# 00B-001.net
KiCad netlist of a schematic drawn in EAGLE
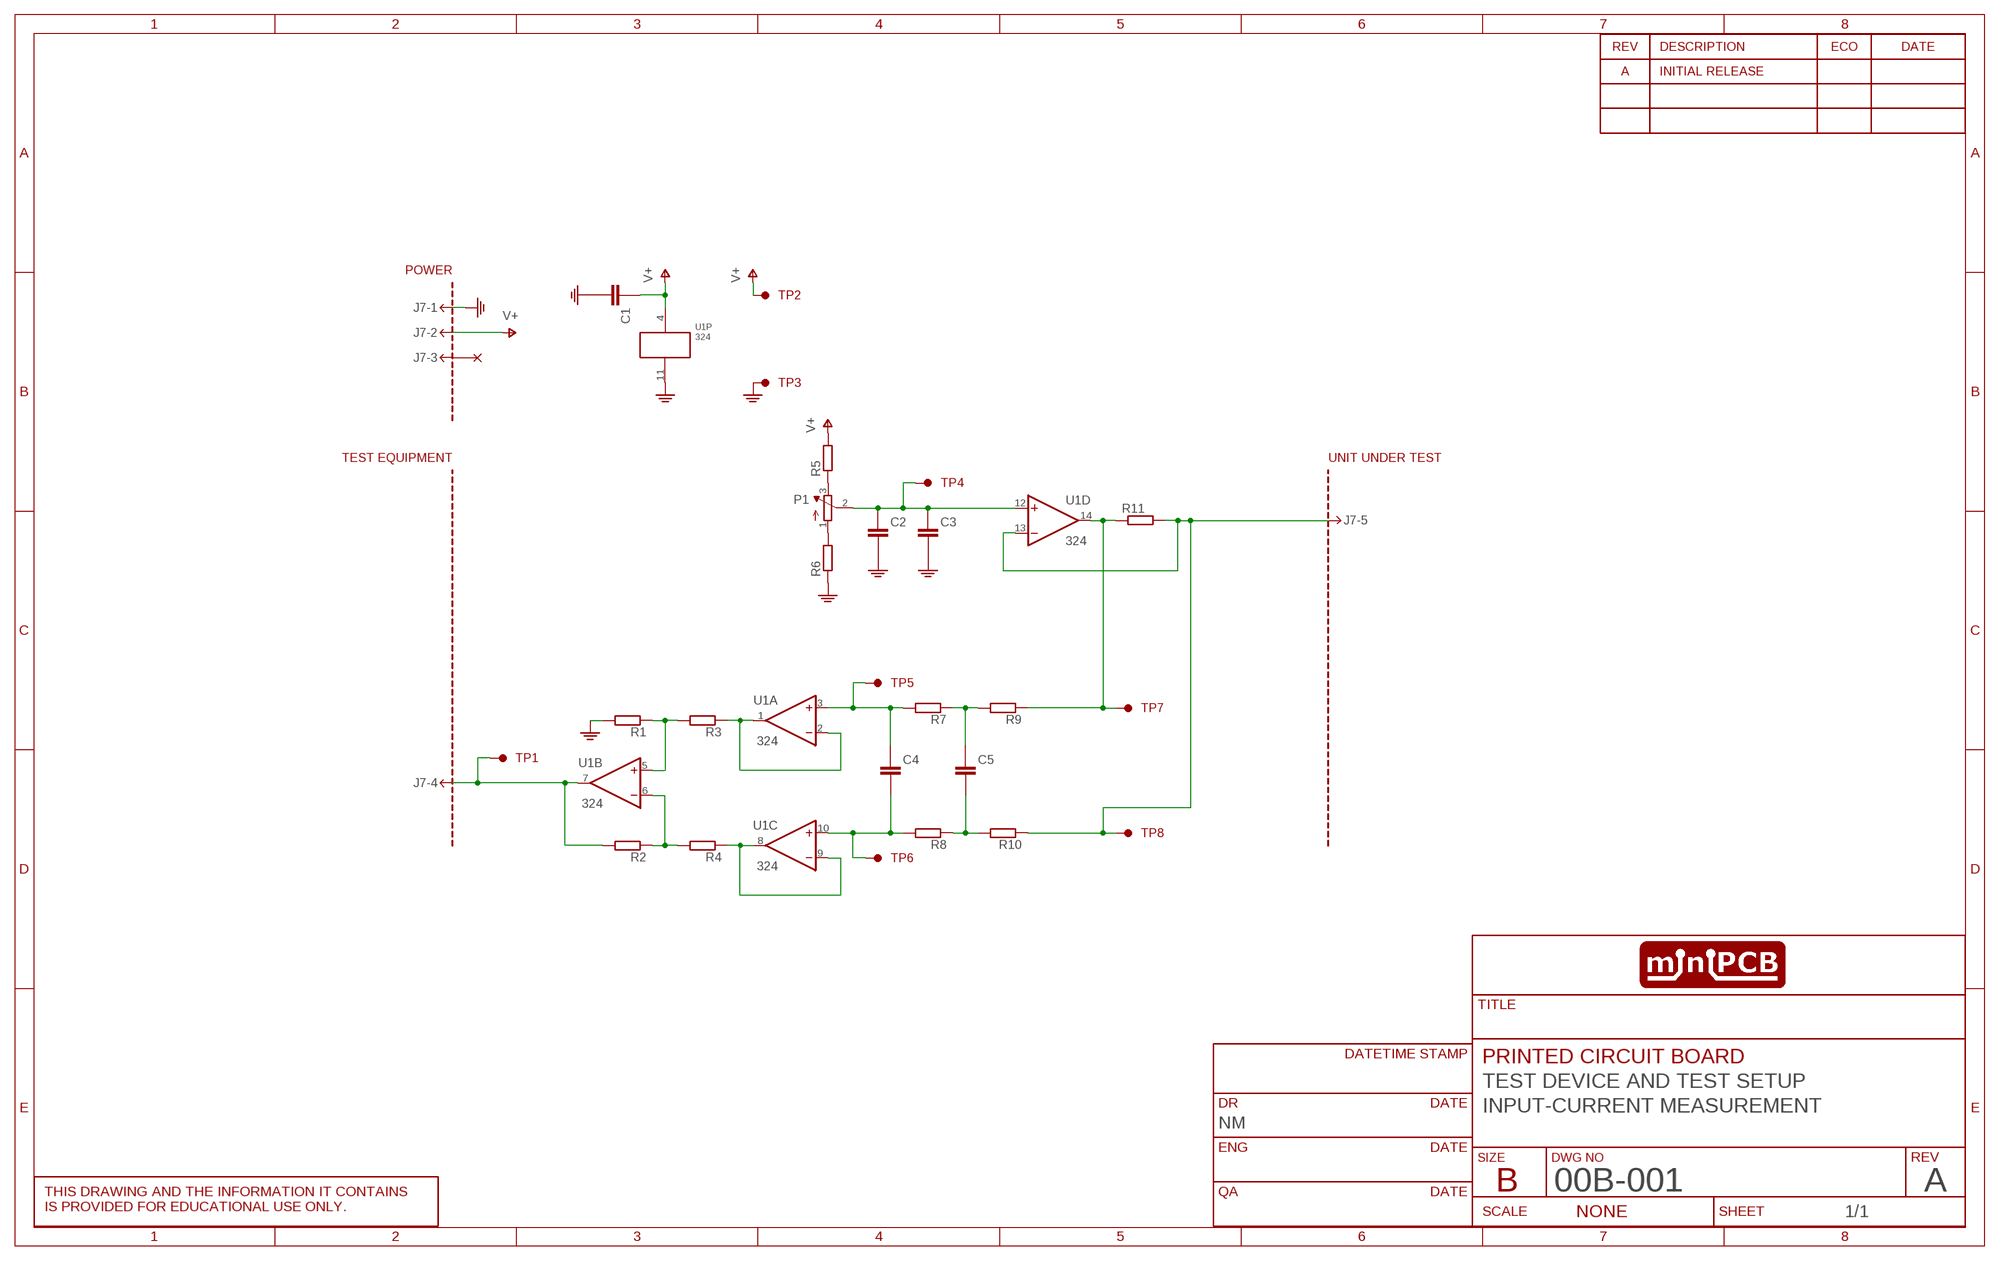
[diagram p0: schematic, sheet 1]

(export (version "E")
  (design (tool "Eeschema 10.0.6"))
  (components
    (comp (ref "C1")
      (value "1u")
      (footprint "eagle-import:C050-024X044")
      (libsource (lib "eagle-import") (part "CAPACITORTHD"))
    )
    (comp (ref "C2")
      (value "CAPACITOR_10")
      (footprint "eagle-import:C5MM")
      (libsource (lib "eagle-import") (part "CAPACITOR_10"))
    )
    (comp (ref "C3")
      (value "CAPACITORTHD")
      (footprint "eagle-import:C050-024X044")
      (libsource (lib "eagle-import") (part "CAPACITORTHD"))
    )
    (comp (ref "C4")
      (value "CAPACITORTHD")
      (footprint "eagle-import:C050-024X044")
      (libsource (lib "eagle-import") (part "CAPACITORTHD"))
    )
    (comp (ref "C5")
      (value "CAPACITORTHD")
      (footprint "eagle-import:C050-024X044")
      (libsource (lib "eagle-import") (part "CAPACITORTHD"))
    )
    (comp (ref "J7-")
      (value "MINIPCB_5P50X50")
      (footprint "eagle-import:MINIPCB_5P_50X50MM")
      (fields (field (name "PART_NUMBER") "00B-001"))
      (libsource (lib "eagle-import") (part "MINIPCB_5P50X50"))
    )
    (comp (ref "P1")
      (value "TRIMPOT0.100THD")
      (footprint "eagle-import:TRIM_0100")
      (libsource (lib "eagle-import") (part "TRIMPOT0.100THD"))
    )
    (comp (ref "R1")
      (value "RESISTOR10MM")
      (footprint "eagle-import:0207_10")
      (libsource (lib "eagle-import") (part "RESISTOR10MM"))
    )
    (comp (ref "R2")
      (value "RESISTOR10MM")
      (footprint "eagle-import:0207_10")
      (libsource (lib "eagle-import") (part "RESISTOR10MM"))
    )
    (comp (ref "R3")
      (value "RESISTOR10MM")
      (footprint "eagle-import:0207_10")
      (libsource (lib "eagle-import") (part "RESISTOR10MM"))
    )
    (comp (ref "R4")
      (value "RESISTOR10MM")
      (footprint "eagle-import:0207_10")
      (libsource (lib "eagle-import") (part "RESISTOR10MM"))
    )
    (comp (ref "R5")
      (value "RESISTOR10MM")
      (footprint "eagle-import:0207_10")
      (libsource (lib "eagle-import") (part "RESISTOR10MM"))
    )
    (comp (ref "R6")
      (value "RESISTOR10MM")
      (footprint "eagle-import:0207_10")
      (libsource (lib "eagle-import") (part "RESISTOR10MM"))
    )
    (comp (ref "R7")
      (value "RESISTOR10MM")
      (footprint "eagle-import:0207_10")
      (libsource (lib "eagle-import") (part "RESISTOR10MM"))
    )
    (comp (ref "R8")
      (value "RESISTOR10MM")
      (footprint "eagle-import:0207_10")
      (libsource (lib "eagle-import") (part "RESISTOR10MM"))
    )
    (comp (ref "R9")
      (value "RESISTOR10MM")
      (footprint "eagle-import:0207_10")
      (libsource (lib "eagle-import") (part "RESISTOR10MM"))
    )
    (comp (ref "R10")
      (value "RESISTOR10MM")
      (footprint "eagle-import:0207_10")
      (libsource (lib "eagle-import") (part "RESISTOR10MM"))
    )
    (comp (ref "R11")
      (value "RESISTOR10MM")
      (footprint "eagle-import:0207_10")
      (libsource (lib "eagle-import") (part "RESISTOR10MM"))
    )
    (comp (ref "TP1")
      (value "TESTPOINTKE5000-SMTEXT")
      (footprint "eagle-import:PINS_1_TESTPOINT_KE5000_NOTEXT")
      (libsource (lib "eagle-import") (part "TESTPOINTKE5000-SMTEXT"))
    )
    (comp (ref "TP2")
      (value "TESTPOINTKE5000-SMTEXT")
      (footprint "eagle-import:PINS_1_TESTPOINT_KE5000_NOTEXT")
      (libsource (lib "eagle-import") (part "TESTPOINTKE5000-SMTEXT"))
    )
    (comp (ref "TP3")
      (value "TESTPOINTKE5000-SMTEXT")
      (footprint "eagle-import:PINS_1_TESTPOINT_KE5000_NOTEXT")
      (libsource (lib "eagle-import") (part "TESTPOINTKE5000-SMTEXT"))
    )
    (comp (ref "TP4")
      (value "TESTPOINTKE5000-SMTEXT")
      (footprint "eagle-import:PINS_1_TESTPOINT_KE5000_NOTEXT")
      (libsource (lib "eagle-import") (part "TESTPOINTKE5000-SMTEXT"))
    )
    (comp (ref "TP5")
      (value "TESTPOINTKE5000-SMTEXT")
      (footprint "eagle-import:PINS_1_TESTPOINT_KE5000_NOTEXT")
      (libsource (lib "eagle-import") (part "TESTPOINTKE5000-SMTEXT"))
    )
    (comp (ref "TP6")
      (value "TESTPOINTKE5000-SMTEXT")
      (footprint "eagle-import:PINS_1_TESTPOINT_KE5000_NOTEXT")
      (libsource (lib "eagle-import") (part "TESTPOINTKE5000-SMTEXT"))
    )
    (comp (ref "TP7")
      (value "TESTPOINTKE5000-SMTEXT")
      (footprint "eagle-import:PINS_1_TESTPOINT_KE5000_NOTEXT")
      (libsource (lib "eagle-import") (part "TESTPOINTKE5000-SMTEXT"))
    )
    (comp (ref "TP8")
      (value "TESTPOINTKE5000-SMTEXT")
      (footprint "eagle-import:PINS_1_TESTPOINT_KE5000_NOTEXT")
      (libsource (lib "eagle-import") (part "TESTPOINTKE5000-SMTEXT"))
    )
    (comp (ref "U1")
      (value "324")
      (footprint "eagle-import:DIL14")
      (libsource (lib "eagle-import") (part "OPAMP_QUADTHD"))
    )
  )
  (nets
    (net (code "1") (name "GND") (class "Default")
      (node (ref "C1") (pin "2") (pinfunction "-_2") (pintype "passive"))
      (node (ref "C2") (pin "-") (pinfunction "-_-") (pintype "passive"))
      (node (ref "C3") (pin "2") (pinfunction "-_2") (pintype "passive"))
      (node (ref "J7-") (pin "1") (pinfunction "1_1") (pintype "bidirectional"))
      (node (ref "R1") (pin "2") (pinfunction "2_2") (pintype "passive"))
      (node (ref "R6") (pin "1") (pinfunction "1_1") (pintype "passive"))
      (node (ref "TP3") (pin "1") (pinfunction "1_1") (pintype "bidirectional"))
      (node (ref "U1") (pin "11") (pinfunction "V-_11") (pintype "power_in"))
    )
    (net (code "2") (name "Net-(C3-+)") (class "Default")
      (node (ref "C2") (pin "+") (pinfunction "+_+") (pintype "passive"))
      (node (ref "C3") (pin "1") (pinfunction "+_1") (pintype "passive"))
      (node (ref "P1") (pin "2") (pinfunction "S_2") (pintype "passive"))
      (node (ref "TP4") (pin "1") (pinfunction "1_1") (pintype "bidirectional"))
      (node (ref "U1") (pin "12") (pinfunction "+IN_12") (pintype "input"))
    )
    (net (code "3") (name "Net-(C4-+)") (class "Default")
      (node (ref "C4") (pin "1") (pinfunction "+_1") (pintype "passive"))
      (node (ref "R7") (pin "2") (pinfunction "2_2") (pintype "passive"))
      (node (ref "TP5") (pin "1") (pinfunction "1_1") (pintype "bidirectional"))
      (node (ref "U1") (pin "3") (pinfunction "+IN_3") (pintype "input"))
    )
    (net (code "4") (name "Net-(C4--)") (class "Default")
      (node (ref "C4") (pin "2") (pinfunction "-_2") (pintype "passive"))
      (node (ref "R8") (pin "2") (pinfunction "2_2") (pintype "passive"))
      (node (ref "TP6") (pin "1") (pinfunction "1_1") (pintype "bidirectional"))
      (node (ref "U1") (pin "10") (pinfunction "+IN_10") (pintype "input"))
    )
    (net (code "5") (name "Net-(C5-+)") (class "Default")
      (node (ref "C5") (pin "1") (pinfunction "+_1") (pintype "passive"))
      (node (ref "R7") (pin "1") (pinfunction "1_1") (pintype "passive"))
      (node (ref "R9") (pin "2") (pinfunction "2_2") (pintype "passive"))
    )
    (net (code "6") (name "Net-(C5--)") (class "Default")
      (node (ref "C5") (pin "2") (pinfunction "-_2") (pintype "passive"))
      (node (ref "R10") (pin "2") (pinfunction "2_2") (pintype "passive"))
      (node (ref "R8") (pin "1") (pinfunction "1_1") (pintype "passive"))
    )
    (net (code "7") (name "Net-(J7-D-1)") (class "Default")
      (node (ref "J7-") (pin "4") (pinfunction "1_4") (pintype "bidirectional"))
      (node (ref "R2") (pin "2") (pinfunction "2_2") (pintype "passive"))
      (node (ref "TP1") (pin "1") (pinfunction "1_1") (pintype "bidirectional"))
      (node (ref "U1") (pin "7") (pinfunction "OUT_7") (pintype "output"))
    )
    (net (code "8") (name "Net-(J7-H-1)") (class "Default")
      (node (ref "J7-") (pin "5") (pinfunction "1_5") (pintype "bidirectional"))
      (node (ref "R10") (pin "1") (pinfunction "1_1") (pintype "passive"))
      (node (ref "R11") (pin "2") (pinfunction "2_2") (pintype "passive"))
      (node (ref "TP8") (pin "1") (pinfunction "1_1") (pintype "bidirectional"))
      (node (ref "U1") (pin "13") (pinfunction "-IN_13") (pintype "input"))
    )
    (net (code "9") (name "Net-(P1-A)") (class "Default")
      (node (ref "P1") (pin "1") (pinfunction "A_1") (pintype "passive"))
      (node (ref "R6") (pin "2") (pinfunction "2_2") (pintype "passive"))
    )
    (net (code "10") (name "Net-(P1-E)") (class "Default")
      (node (ref "P1") (pin "3") (pinfunction "E_3") (pintype "passive"))
      (node (ref "R5") (pin "1") (pinfunction "1_1") (pintype "passive"))
    )
    (net (code "11") (name "Net-(U1A--IN)") (class "Default")
      (node (ref "R3") (pin "1") (pinfunction "1_1") (pintype "passive"))
      (node (ref "U1") (pin "1") (pinfunction "OUT_1") (pintype "output"))
      (node (ref "U1") (pin "2") (pinfunction "-IN_2") (pintype "input"))
    )
    (net (code "12") (name "Net-(U1B-+IN)") (class "Default")
      (node (ref "R1") (pin "1") (pinfunction "1_1") (pintype "passive"))
      (node (ref "R3") (pin "2") (pinfunction "2_2") (pintype "passive"))
      (node (ref "U1") (pin "5") (pinfunction "+IN_5") (pintype "input"))
    )
    (net (code "13") (name "Net-(U1B--IN)") (class "Default")
      (node (ref "R2") (pin "1") (pinfunction "1_1") (pintype "passive"))
      (node (ref "R4") (pin "2") (pinfunction "2_2") (pintype "passive"))
      (node (ref "U1") (pin "6") (pinfunction "-IN_6") (pintype "input"))
    )
    (net (code "14") (name "Net-(U1C--IN)") (class "Default")
      (node (ref "R4") (pin "1") (pinfunction "1_1") (pintype "passive"))
      (node (ref "U1") (pin "8") (pinfunction "OUT_8") (pintype "output"))
      (node (ref "U1") (pin "9") (pinfunction "-IN_9") (pintype "input"))
    )
    (net (code "15") (name "Net-(U1D-OUT)") (class "Default")
      (node (ref "R11") (pin "1") (pinfunction "1_1") (pintype "passive"))
      (node (ref "R9") (pin "1") (pinfunction "1_1") (pintype "passive"))
      (node (ref "TP7") (pin "1") (pinfunction "1_1") (pintype "bidirectional"))
      (node (ref "U1") (pin "14") (pinfunction "OUT_14") (pintype "output"))
    )
    (net (code "16") (name "V+") (class "Default")
      (node (ref "C1") (pin "1") (pinfunction "+_1") (pintype "passive"))
      (node (ref "J7-") (pin "2") (pinfunction "1_2") (pintype "bidirectional"))
      (node (ref "R5") (pin "2") (pinfunction "2_2") (pintype "passive"))
      (node (ref "TP2") (pin "1") (pinfunction "1_1") (pintype "bidirectional"))
      (node (ref "U1") (pin "4") (pinfunction "V+_4") (pintype "power_in"))
    )
    (net (code "17") (name "unconnected-(J7-C-1-Pad3)") (class "Default")
      (node (ref "J7-") (pin "3") (pinfunction "1_3") (pintype "bidirectional"))
    )
  )
)
